# SchemaCentrale.net
KiCad netlist of a schematic drawn in Altium Designer
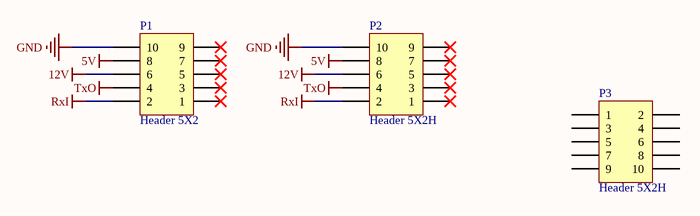
[diagram p0: SchemaCentrale.SchDoc]

(export (version "E")
  (design (tool "Eeschema 10.0.6"))
  (components
    (comp (ref "P1")
      (value "Header 5X2")
      (footprint "Header10Coude")
      (description "Header, 5-Pin, Dual row")
      (fields (field (name "PUBLISHER") "Altium Limited"))
      (libsource (lib "Miscellaneous Connectors") (part "Header 5X2"))
    )
    (comp (ref "P2")
      (value "Header 5X2H")
      (footprint "HEADERDroit")
      (description "Header, 5-Pin, Dual row, Right Angle")
      (fields (field (name "PUBLISHER") "Altium Limited"))
      (libsource (lib "") (part "Header 5X2H_1"))
    )
    (comp (ref "P3")
      (value "Header 5X2H")
      (footprint "HEADERACHEVAL")
      (description "Header, 5-Pin, Dual row, Right Angle")
      (fields (field (name "PUBLISHER") "Altium Limited"))
      (libsource (lib "Miscellaneous Connectors") (part "Header 5X2H"))
    )
  )
  (nets
    (net (code "1") (name "5V") (class "Default")
      (node (ref "P1") (pin "8") (pinfunction "8_8") (pintype "passive"))
      (node (ref "P2") (pin "8") (pinfunction "8_8") (pintype "passive"))
    )
    (net (code "2") (name "12V") (class "Default")
      (node (ref "P1") (pin "6") (pinfunction "6_6") (pintype "passive"))
      (node (ref "P2") (pin "6") (pinfunction "6_6") (pintype "passive"))
    )
    (net (code "3") (name "GND") (class "Default")
      (node (ref "P1") (pin "10") (pinfunction "10_10") (pintype "passive"))
      (node (ref "P2") (pin "10") (pinfunction "10_10") (pintype "passive"))
    )
    (net (code "4") (name "RxI") (class "Default")
      (node (ref "P1") (pin "2") (pinfunction "2_2") (pintype "passive"))
      (node (ref "P2") (pin "2") (pinfunction "2_2") (pintype "passive"))
    )
    (net (code "5") (name "TxO") (class "Default")
      (node (ref "P1") (pin "4") (pinfunction "4_4") (pintype "passive"))
      (node (ref "P2") (pin "4") (pinfunction "4_4") (pintype "passive"))
    )
    (net (code "6") (name "unconnected-(P1-Pad1)") (class "Default")
      (node (ref "P1") (pin "1") (pinfunction "1_1") (pintype "passive+no_connect"))
    )
    (net (code "7") (name "unconnected-(P1-Pad3)") (class "Default")
      (node (ref "P1") (pin "3") (pinfunction "3_3") (pintype "passive+no_connect"))
    )
    (net (code "8") (name "unconnected-(P1-Pad5)") (class "Default")
      (node (ref "P1") (pin "5") (pinfunction "5_5") (pintype "passive+no_connect"))
    )
    (net (code "9") (name "unconnected-(P1-Pad7)") (class "Default")
      (node (ref "P1") (pin "7") (pinfunction "7_7") (pintype "passive+no_connect"))
    )
    (net (code "10") (name "unconnected-(P1-Pad9)") (class "Default")
      (node (ref "P1") (pin "9") (pinfunction "9_9") (pintype "passive+no_connect"))
    )
    (net (code "11") (name "unconnected-(P2-Pad1)") (class "Default")
      (node (ref "P2") (pin "1") (pinfunction "1_1") (pintype "passive+no_connect"))
    )
    (net (code "12") (name "unconnected-(P2-Pad3)") (class "Default")
      (node (ref "P2") (pin "3") (pinfunction "3_3") (pintype "passive+no_connect"))
    )
    (net (code "13") (name "unconnected-(P2-Pad5)") (class "Default")
      (node (ref "P2") (pin "5") (pinfunction "5_5") (pintype "passive+no_connect"))
    )
    (net (code "14") (name "unconnected-(P2-Pad7)") (class "Default")
      (node (ref "P2") (pin "7") (pinfunction "7_7") (pintype "passive+no_connect"))
    )
    (net (code "15") (name "unconnected-(P2-Pad9)") (class "Default")
      (node (ref "P2") (pin "9") (pinfunction "9_9") (pintype "passive+no_connect"))
    )
    (net (code "16") (name "unconnected-(P3-Pad1)") (class "Default")
      (node (ref "P3") (pin "1") (pinfunction "1_1") (pintype "passive"))
    )
    (net (code "17") (name "unconnected-(P3-Pad2)") (class "Default")
      (node (ref "P3") (pin "2") (pinfunction "2_2") (pintype "passive"))
    )
    (net (code "18") (name "unconnected-(P3-Pad3)") (class "Default")
      (node (ref "P3") (pin "3") (pinfunction "3_3") (pintype "passive"))
    )
    (net (code "19") (name "unconnected-(P3-Pad4)") (class "Default")
      (node (ref "P3") (pin "4") (pinfunction "4_4") (pintype "passive"))
    )
    (net (code "20") (name "unconnected-(P3-Pad5)") (class "Default")
      (node (ref "P3") (pin "5") (pinfunction "5_5") (pintype "passive"))
    )
    (net (code "21") (name "unconnected-(P3-Pad6)") (class "Default")
      (node (ref "P3") (pin "6") (pinfunction "6_6") (pintype "passive"))
    )
    (net (code "22") (name "unconnected-(P3-Pad7)") (class "Default")
      (node (ref "P3") (pin "7") (pinfunction "7_7") (pintype "passive"))
    )
    (net (code "23") (name "unconnected-(P3-Pad8)") (class "Default")
      (node (ref "P3") (pin "8") (pinfunction "8_8") (pintype "passive"))
    )
    (net (code "24") (name "unconnected-(P3-Pad9)") (class "Default")
      (node (ref "P3") (pin "9") (pinfunction "9_9") (pintype "passive"))
    )
    (net (code "25") (name "unconnected-(P3-Pad10)") (class "Default")
      (node (ref "P3") (pin "10") (pinfunction "10_10") (pintype "passive"))
    )
  )
)
